# pinoccio-backpack.net
KiCad netlist of a schematic drawn in EAGLE
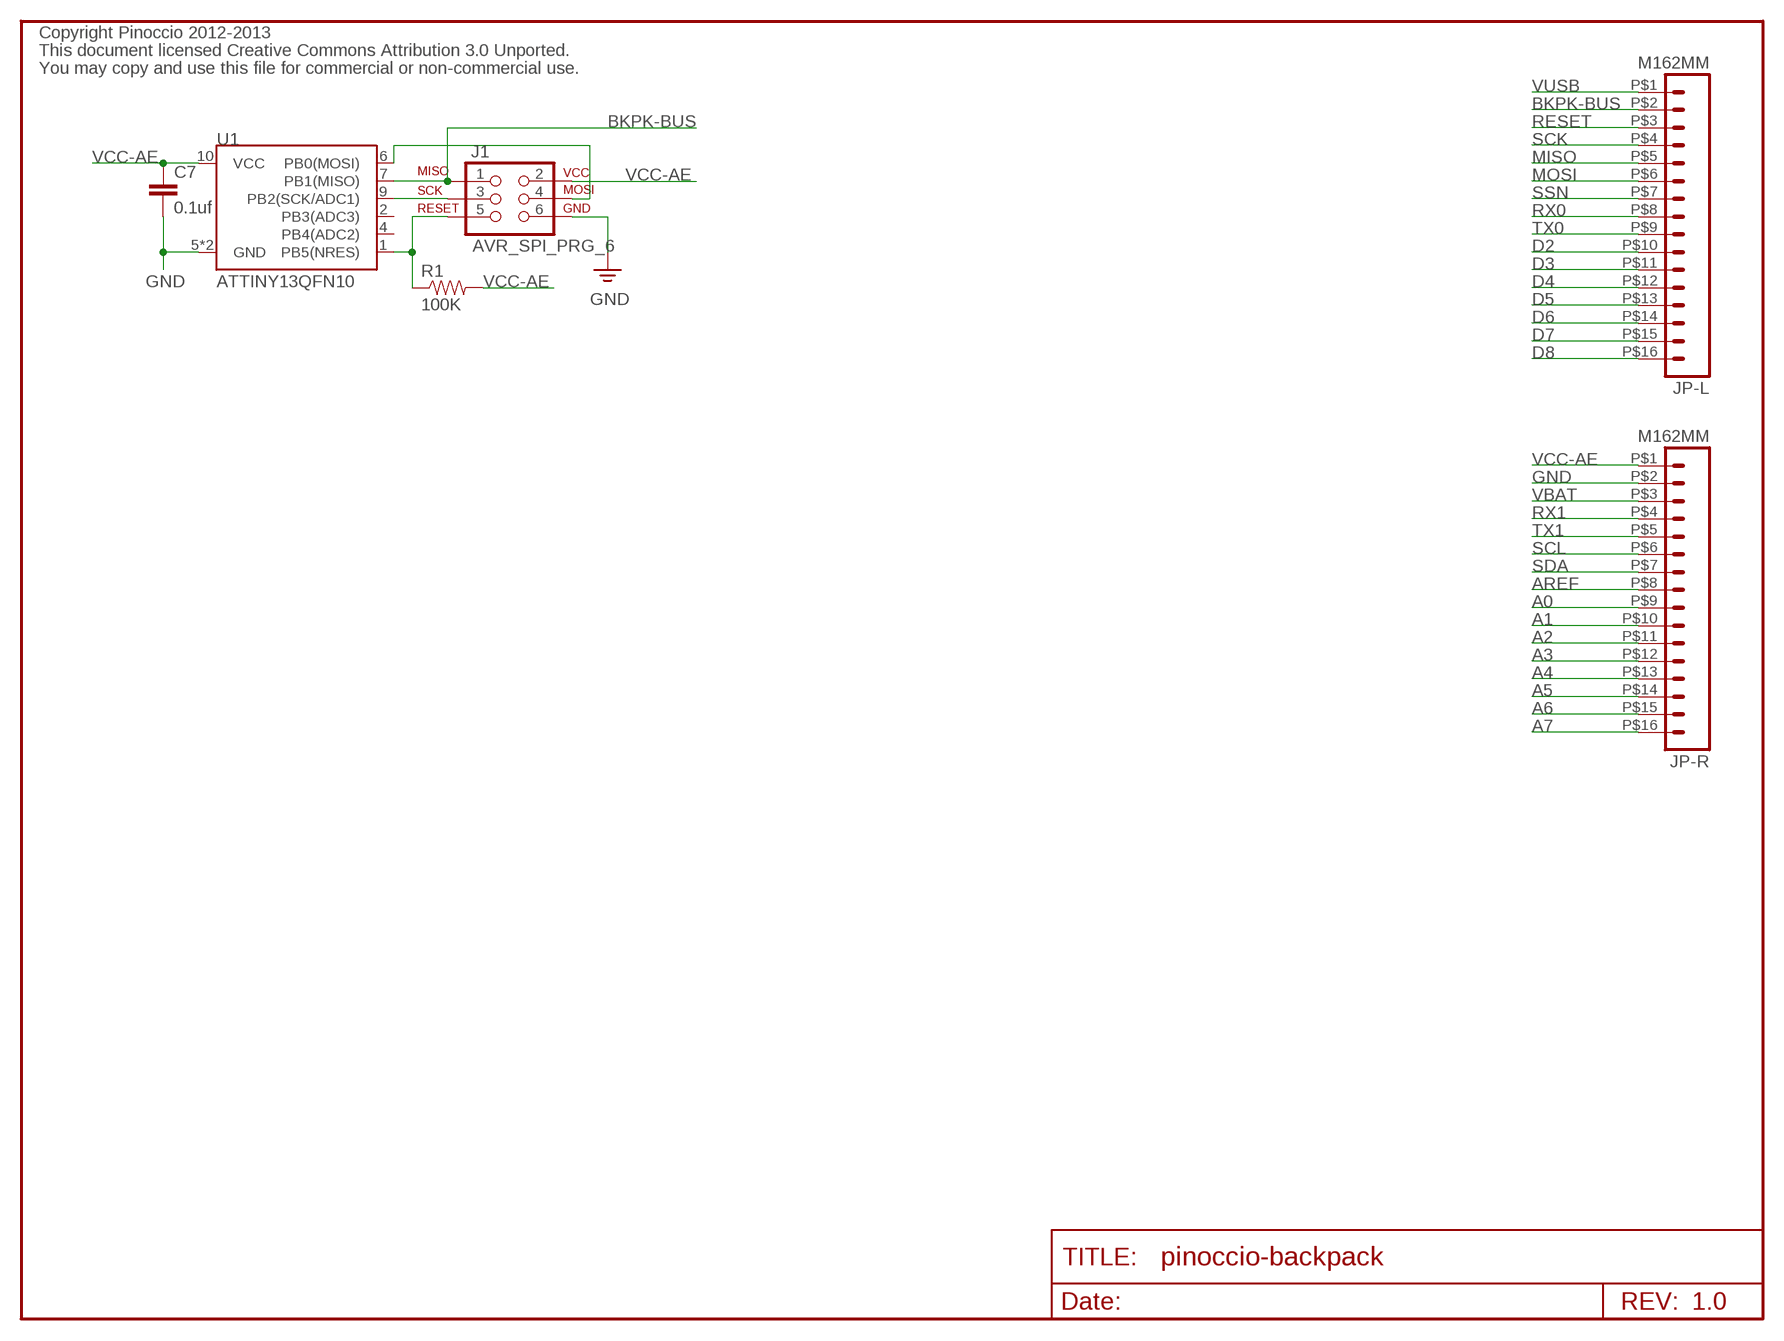
[diagram p0: schematic, sheet 1]

(export (version "E")
  (design (tool "Eeschema 10.0.6"))
  (components
    (comp (ref "C7")
      (value "0.1uf")
      (footprint "eagle-import:0402-CAP")
      (libsource (lib "eagle-import") (part "CAP0402-CAP"))
    )
    (comp (ref "J1")
      (value "AVR_SPI_PRG_6")
      (footprint "eagle-import:2X3-PAD")
      (libsource (lib "eagle-import") (part "AVR_SPI_PRG_6"))
    )
    (comp (ref "JP-L")
      (value "M162MM")
      (footprint "eagle-import:1X16_2MM")
      (libsource (lib "eagle-import") (part "M162MM"))
    )
    (comp (ref "JP-R")
      (value "M162MM")
      (footprint "eagle-import:1X16_2MM")
      (libsource (lib "eagle-import") (part "M162MM"))
    )
    (comp (ref "R1")
      (value "100K")
      (footprint "eagle-import:0402-RES")
      (libsource (lib "eagle-import") (part "RESISTOR0402-RES"))
    )
    (comp (ref "U1")
      (value "ATTINY13QFN10")
      (footprint "eagle-import:QFN-10")
      (libsource (lib "eagle-import") (part "ATTINY13QFN10"))
    )
  )
  (nets
    (net (code "1") (name "/A0") (class "Default")
      (node (ref "JP-R") (pin "P$9") (pinfunction "9_P$9") (pintype "passive"))
    )
    (net (code "2") (name "/A1") (class "Default")
      (node (ref "JP-R") (pin "P$10") (pinfunction "10_P$10") (pintype "passive"))
    )
    (net (code "3") (name "/A2") (class "Default")
      (node (ref "JP-R") (pin "P$11") (pinfunction "11_P$11") (pintype "passive"))
    )
    (net (code "4") (name "/A3") (class "Default")
      (node (ref "JP-R") (pin "P$12") (pinfunction "12_P$12") (pintype "passive"))
    )
    (net (code "5") (name "/A4") (class "Default")
      (node (ref "JP-R") (pin "P$13") (pinfunction "13_P$13") (pintype "passive"))
    )
    (net (code "6") (name "/A5") (class "Default")
      (node (ref "JP-R") (pin "P$14") (pinfunction "14_P$14") (pintype "passive"))
    )
    (net (code "7") (name "/A6") (class "Default")
      (node (ref "JP-R") (pin "P$15") (pinfunction "15_P$15") (pintype "passive"))
    )
    (net (code "8") (name "/A7") (class "Default")
      (node (ref "JP-R") (pin "P$16") (pinfunction "16_P$16") (pintype "passive"))
    )
    (net (code "9") (name "/AREF") (class "Default")
      (node (ref "JP-R") (pin "P$8") (pinfunction "8_P$8") (pintype "passive"))
    )
    (net (code "10") (name "/BKPK-BUS") (class "Default")
      (node (ref "J1") (pin "1") (pinfunction "1_1") (pintype "passive"))
      (node (ref "JP-L") (pin "P$2") (pinfunction "2_P$2") (pintype "passive"))
      (node (ref "U1") (pin "7") (pinfunction "PB1(MISO)_7") (pintype "bidirectional"))
    )
    (net (code "11") (name "/D2") (class "Default")
      (node (ref "JP-L") (pin "P$10") (pinfunction "10_P$10") (pintype "passive"))
    )
    (net (code "12") (name "/D3") (class "Default")
      (node (ref "JP-L") (pin "P$11") (pinfunction "11_P$11") (pintype "passive"))
    )
    (net (code "13") (name "/D4") (class "Default")
      (node (ref "JP-L") (pin "P$12") (pinfunction "12_P$12") (pintype "passive"))
    )
    (net (code "14") (name "/D5") (class "Default")
      (node (ref "JP-L") (pin "P$13") (pinfunction "13_P$13") (pintype "passive"))
    )
    (net (code "15") (name "/D6") (class "Default")
      (node (ref "JP-L") (pin "P$14") (pinfunction "14_P$14") (pintype "passive"))
    )
    (net (code "16") (name "/D7") (class "Default")
      (node (ref "JP-L") (pin "P$15") (pinfunction "15_P$15") (pintype "passive"))
    )
    (net (code "17") (name "/D8") (class "Default")
      (node (ref "JP-L") (pin "P$16") (pinfunction "16_P$16") (pintype "passive"))
    )
    (net (code "18") (name "/MISO") (class "Default")
      (node (ref "JP-L") (pin "P$5") (pinfunction "5_P$5") (pintype "passive"))
    )
    (net (code "19") (name "/MOSI") (class "Default")
      (node (ref "JP-L") (pin "P$6") (pinfunction "6_P$6") (pintype "passive"))
    )
    (net (code "20") (name "/RESET") (class "Default")
      (node (ref "JP-L") (pin "P$3") (pinfunction "3_P$3") (pintype "passive"))
    )
    (net (code "21") (name "/RX0") (class "Default")
      (node (ref "JP-L") (pin "P$8") (pinfunction "8_P$8") (pintype "passive"))
    )
    (net (code "22") (name "/RX1") (class "Default")
      (node (ref "JP-R") (pin "P$4") (pinfunction "4_P$4") (pintype "passive"))
    )
    (net (code "23") (name "/SCK") (class "Default")
      (node (ref "JP-L") (pin "P$4") (pinfunction "4_P$4") (pintype "passive"))
    )
    (net (code "24") (name "/SCL") (class "Default")
      (node (ref "JP-R") (pin "P$6") (pinfunction "6_P$6") (pintype "passive"))
    )
    (net (code "25") (name "/SDA") (class "Default")
      (node (ref "JP-R") (pin "P$7") (pinfunction "7_P$7") (pintype "passive"))
    )
    (net (code "26") (name "/SSN") (class "Default")
      (node (ref "JP-L") (pin "P$7") (pinfunction "7_P$7") (pintype "passive"))
    )
    (net (code "27") (name "/TX0") (class "Default")
      (node (ref "JP-L") (pin "P$9") (pinfunction "9_P$9") (pintype "passive"))
    )
    (net (code "28") (name "/TX1") (class "Default")
      (node (ref "JP-R") (pin "P$5") (pinfunction "5_P$5") (pintype "passive"))
    )
    (net (code "29") (name "/VBAT") (class "Default")
      (node (ref "JP-R") (pin "P$3") (pinfunction "3_P$3") (pintype "passive"))
    )
    (net (code "30") (name "/VCC-AE") (class "Default")
      (node (ref "C7") (pin "1") (pinfunction "1_1") (pintype "passive"))
      (node (ref "J1") (pin "2") (pinfunction "2_2") (pintype "passive"))
      (node (ref "JP-R") (pin "P$1") (pinfunction "1_P$1") (pintype "passive"))
      (node (ref "R1") (pin "2") (pinfunction "2_2") (pintype "passive"))
      (node (ref "U1") (pin "10") (pinfunction "VCC_10") (pintype "bidirectional"))
    )
    (net (code "31") (name "/VUSB") (class "Default")
      (node (ref "JP-L") (pin "P$1") (pinfunction "1_P$1") (pintype "passive"))
    )
    (net (code "32") (name "GND") (class "Default")
      (node (ref "C7") (pin "2") (pinfunction "2_2") (pintype "passive"))
      (node (ref "J1") (pin "6") (pinfunction "6_6") (pintype "passive"))
      (node (ref "JP-R") (pin "P$2") (pinfunction "2_P$2") (pintype "passive"))
      (node (ref "U1") (pin "5") (pinfunction "GND_5") (pintype "bidirectional"))
      (node (ref "U1") (pin "EP") (pinfunction "GND_EP") (pintype "bidirectional"))
    )
    (net (code "33") (name "Net-(U1-PB0(MOSI))") (class "Default")
      (node (ref "J1") (pin "4") (pinfunction "4_4") (pintype "passive"))
      (node (ref "U1") (pin "6") (pinfunction "PB0(MOSI)_6") (pintype "bidirectional"))
    )
    (net (code "34") (name "Net-(U1-PB2(SCK{slash}ADC1))") (class "Default")
      (node (ref "J1") (pin "3") (pinfunction "3_3") (pintype "passive"))
      (node (ref "U1") (pin "9") (pinfunction "PB2(SCK/ADC1)_9") (pintype "bidirectional"))
    )
    (net (code "35") (name "Net-(U1-PB5(NRES))") (class "Default")
      (node (ref "J1") (pin "5") (pinfunction "5_5") (pintype "passive"))
      (node (ref "R1") (pin "1") (pinfunction "1_1") (pintype "passive"))
      (node (ref "U1") (pin "1") (pinfunction "PB5(NRES)_1") (pintype "bidirectional"))
    )
    (net (code "36") (name "unconnected-(U1-PB3(ADC3)-Pad2)") (class "Default")
      (node (ref "U1") (pin "2") (pinfunction "PB3(ADC3)_2") (pintype "bidirectional"))
    )
    (net (code "37") (name "unconnected-(U1-PB4(ADC2)-Pad4)") (class "Default")
      (node (ref "U1") (pin "4") (pinfunction "PB4(ADC2)_4") (pintype "bidirectional"))
    )
  )
)
